# TSC_Schema.net
KiCad netlist of a schematic drawn in EAGLE
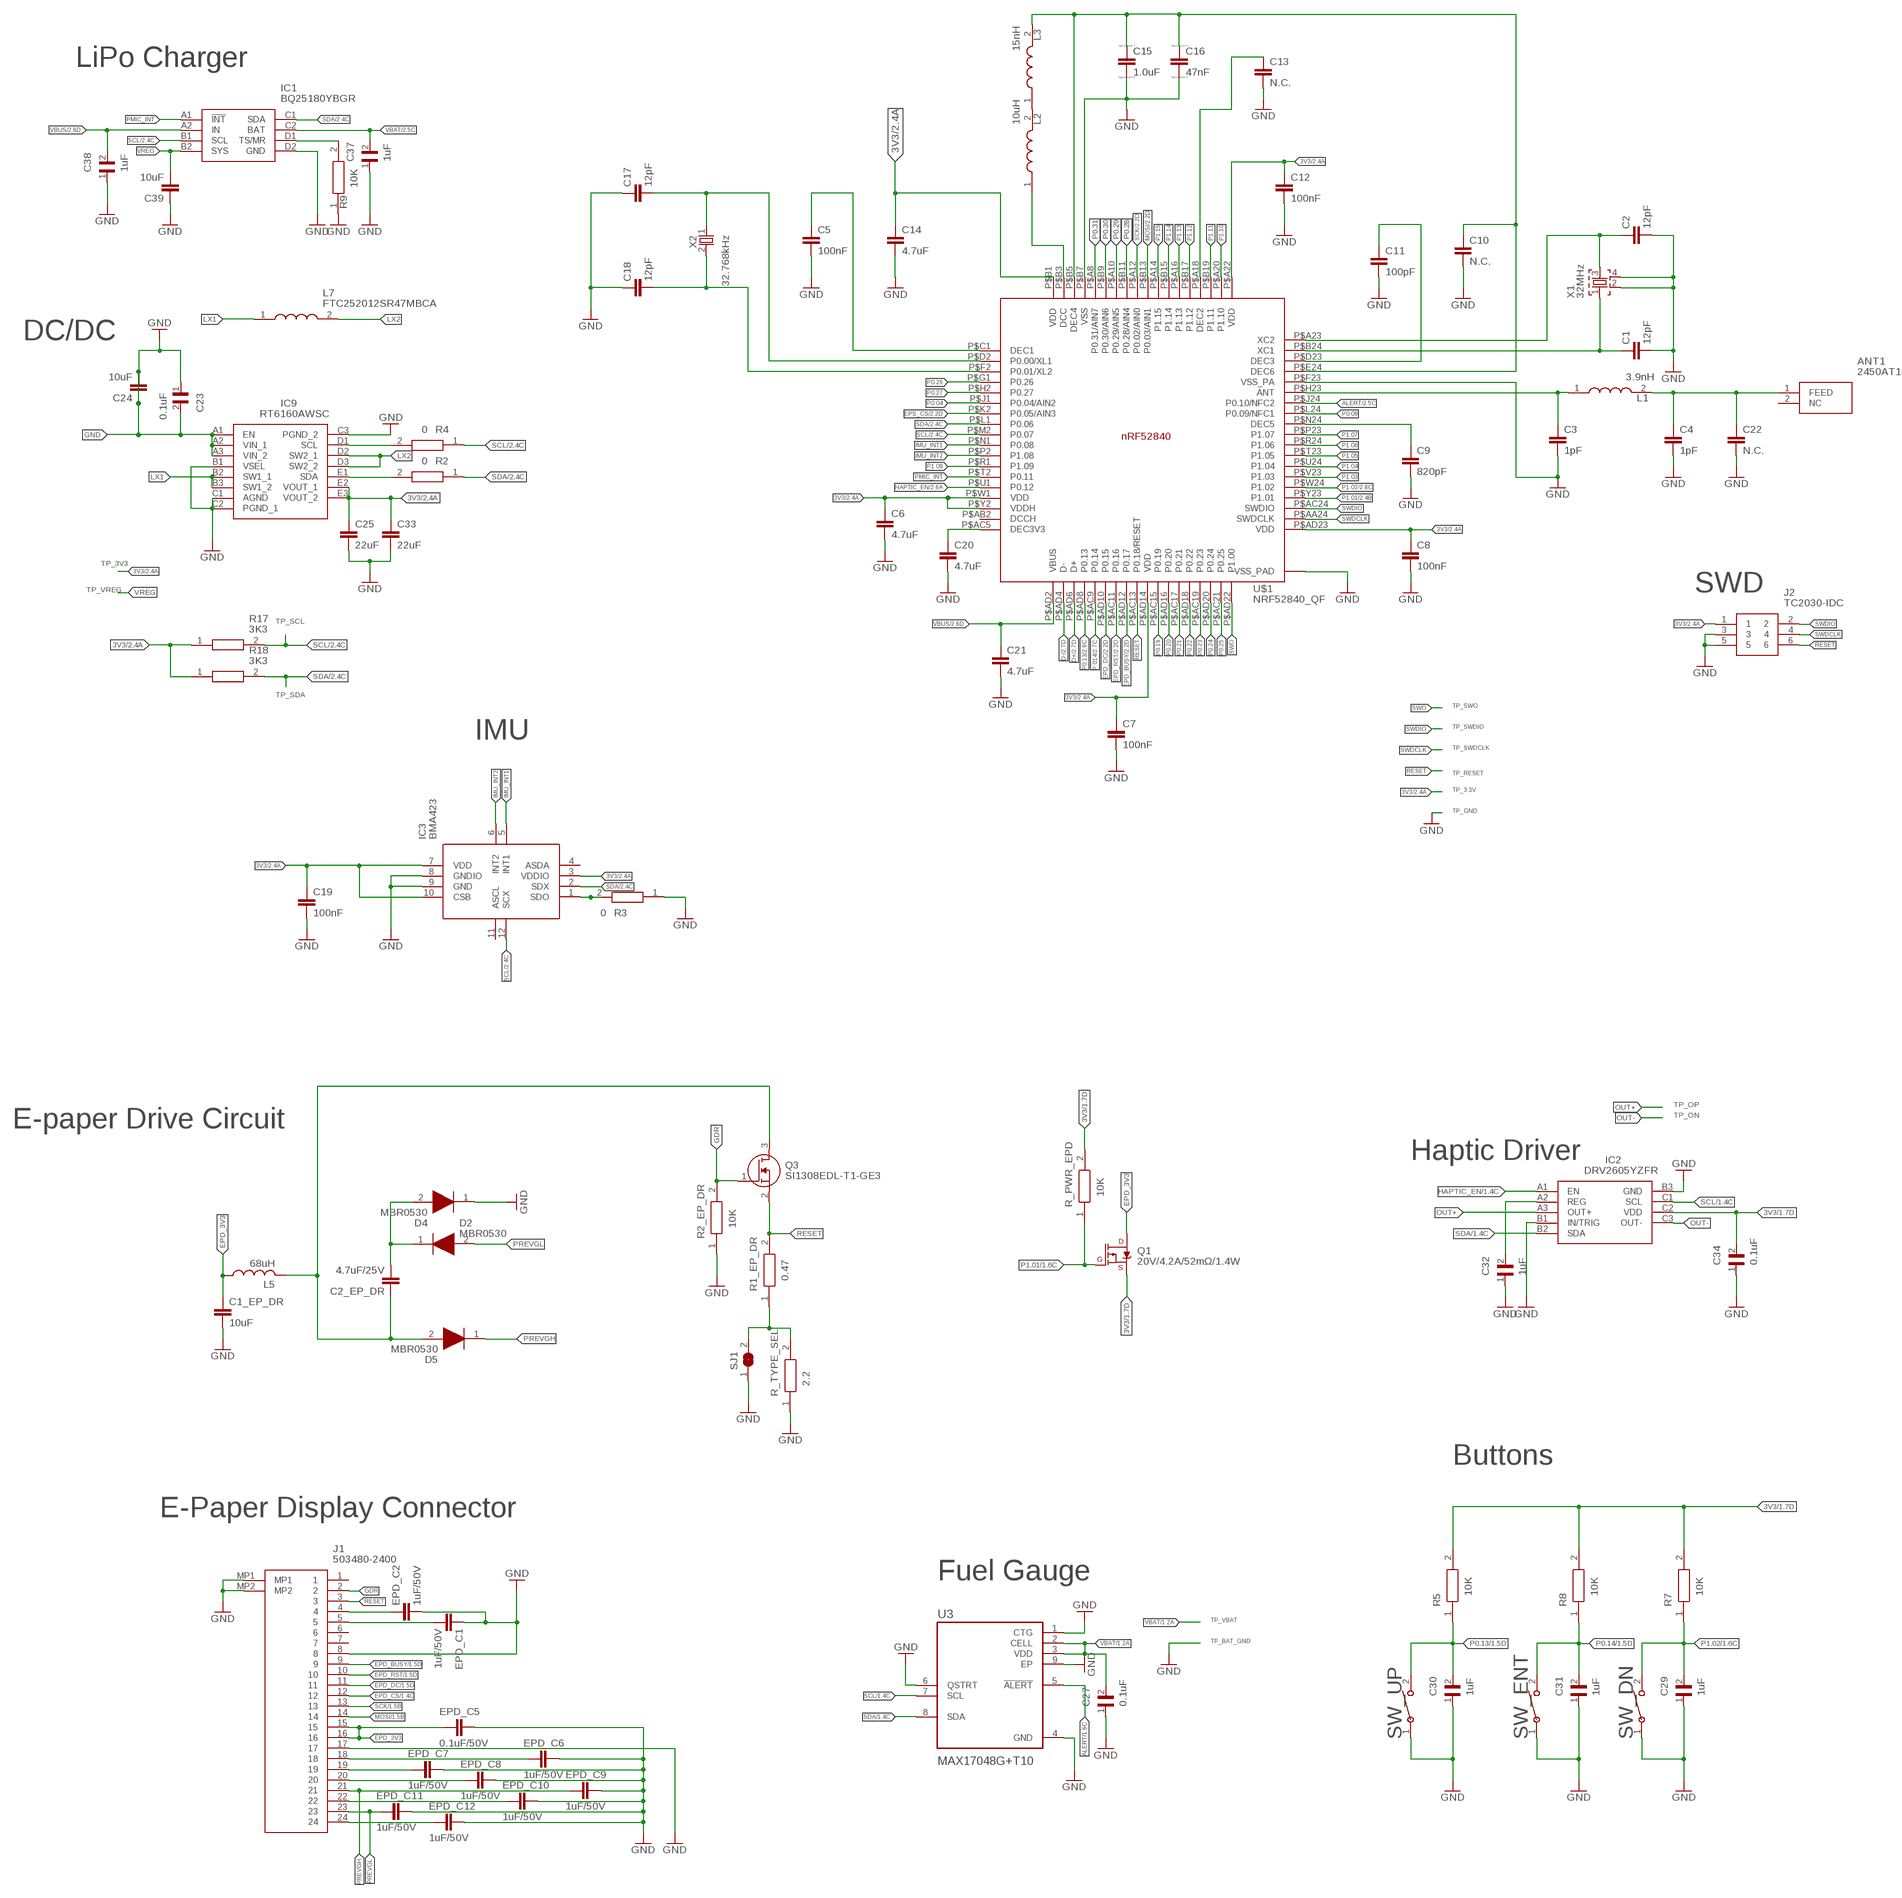
[diagram p0: schematic, sheet 1, part 1 of 2]
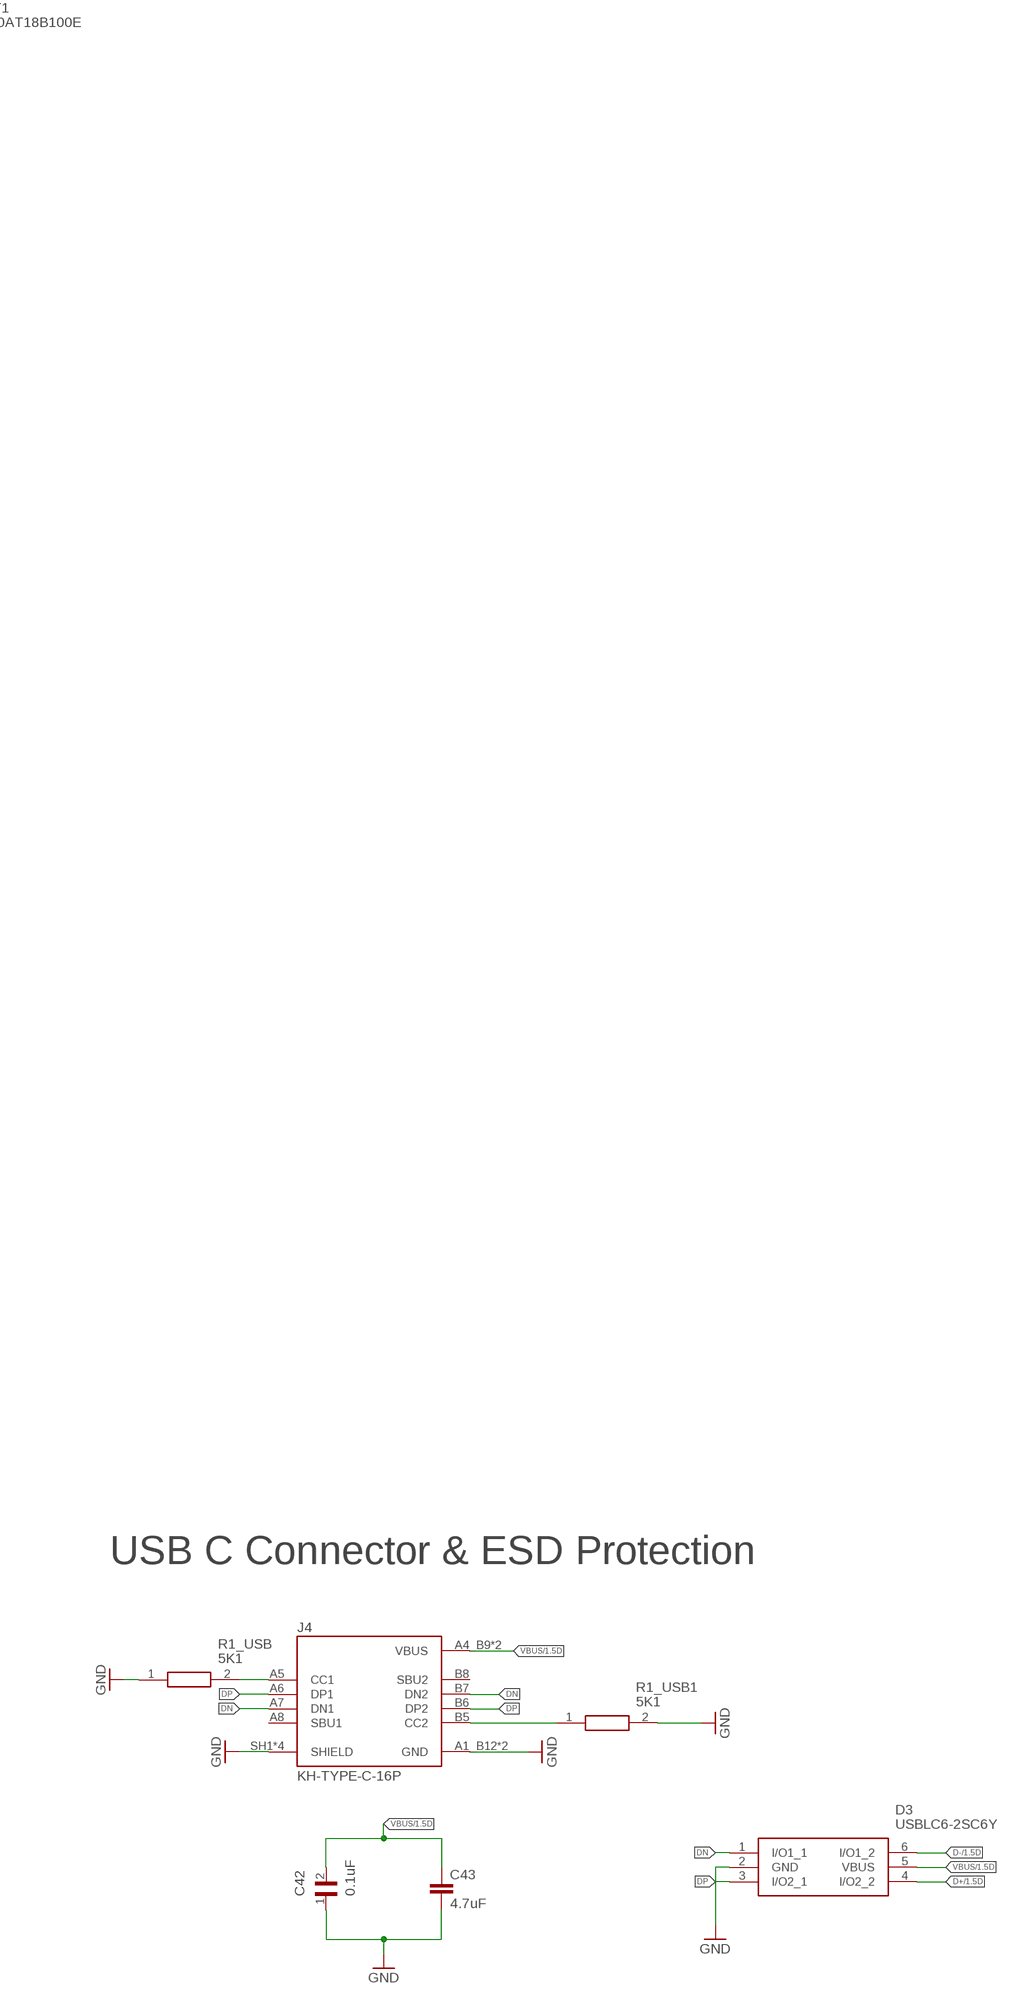
[diagram p1: schematic, sheet 1, part 2 of 2]

(export (version "E")
  (design (tool "Eeschema 10.0.6"))
  (components
    (comp (ref "ANT1")
      (value "2450AT18B100E")
      (footprint "eagle-import:2450AT18B100E_ANTC3216X140N")
      (fields (field (name "MOUSER_PART_NUMBER") "609-2450AT18B100E"))
      (libsource (lib "eagle-import") (part "2450AT18B100E_2450AT18B100E"))
    )
    (comp (ref "C1")
      (value "12pF")
      (footprint "eagle-import:NORDIC_NRF_3_RESC0402_N")
      (libsource (lib "eagle-import") (part "NORDIC_NRF_3_CAPACITOR_0402_N"))
    )
    (comp (ref "C1_EP_DR")
      (value "10uF")
      (footprint "eagle-import:NORDIC_NRF_3_RESC0402_N")
      (libsource (lib "eagle-import") (part "NORDIC_NRF_3_CAPACITOR_0402_N"))
    )
    (comp (ref "C2")
      (value "12pF")
      (footprint "eagle-import:NORDIC_NRF_3_RESC0402_N")
      (libsource (lib "eagle-import") (part "NORDIC_NRF_3_CAPACITOR_0402_N"))
    )
    (comp (ref "C2_EP_DR")
      (value "4.7uF/25V")
      (footprint "eagle-import:NORDIC_NRF_3_RESC0402_N")
      (libsource (lib "eagle-import") (part "NORDIC_NRF_3_CAPACITOR_0402_N"))
    )
    (comp (ref "C3")
      (value "1pF")
      (footprint "eagle-import:NORDIC_NRF_3_RESC0402_N")
      (libsource (lib "eagle-import") (part "NORDIC_NRF_3_CAPACITOR_0402_N"))
    )
    (comp (ref "C4")
      (value "1pF")
      (footprint "eagle-import:NORDIC_NRF_3_RESC0402_N")
      (libsource (lib "eagle-import") (part "NORDIC_NRF_3_CAPACITOR_0402_N"))
    )
    (comp (ref "C5")
      (value "100nF")
      (footprint "eagle-import:NORDIC_NRF_3_RESC0402_N")
      (libsource (lib "eagle-import") (part "NORDIC_NRF_3_CAPACITOR_0402_N"))
    )
    (comp (ref "C6")
      (value "4.7uF")
      (footprint "eagle-import:NORDIC_NRF_3_RESC0402_N")
      (libsource (lib "eagle-import") (part "NORDIC_NRF_3_CAPACITOR_0402_N"))
    )
    (comp (ref "C7")
      (value "100nF")
      (footprint "eagle-import:NORDIC_NRF_3_RESC0402_N")
      (libsource (lib "eagle-import") (part "NORDIC_NRF_3_CAPACITOR_0402_N"))
    )
    (comp (ref "C8")
      (value "100nF")
      (footprint "eagle-import:NORDIC_NRF_3_RESC0402_N")
      (libsource (lib "eagle-import") (part "NORDIC_NRF_3_CAPACITOR_0402_N"))
    )
    (comp (ref "C9")
      (value "820pF")
      (footprint "eagle-import:NORDIC_NRF_3_RESC0402_N")
      (libsource (lib "eagle-import") (part "NORDIC_NRF_3_CAPACITOR_0402_N"))
    )
    (comp (ref "C10")
      (value "N.C.")
      (footprint "eagle-import:NORDIC_NRF_3_RESC0402_N")
      (libsource (lib "eagle-import") (part "NORDIC_NRF_3_CAPACITOR_0402_N"))
    )
    (comp (ref "C11")
      (value "100pF")
      (footprint "eagle-import:NORDIC_NRF_3_RESC0402_N")
      (libsource (lib "eagle-import") (part "NORDIC_NRF_3_CAPACITOR_0402_N"))
    )
    (comp (ref "C12")
      (value "100nF")
      (footprint "eagle-import:NORDIC_NRF_3_RESC0402_N")
      (libsource (lib "eagle-import") (part "NORDIC_NRF_3_CAPACITOR_0402_N"))
    )
    (comp (ref "C13")
      (value "N.C.")
      (footprint "eagle-import:NORDIC_NRF_3_RESC0402_N")
      (libsource (lib "eagle-import") (part "NORDIC_NRF_3_CAPACITOR_0402_N"))
    )
    (comp (ref "C14")
      (value "4.7uF")
      (footprint "eagle-import:NORDIC_NRF_3_RESC0402_N")
      (libsource (lib "eagle-import") (part "NORDIC_NRF_3_CAPACITOR_0402_N"))
    )
    (comp (ref "C15")
      (value "1.0uF")
      (footprint "eagle-import:ESP32_C6_LIBRARY_1_ESP32_WROVER_EAGLE-LTSPICE_C0402")
      (libsource (lib "eagle-import") (part "ESP32_C6_LIBRARY_1_ESP32_WROVER_EAGLE-LTSPICE_CC0402"))
    )
    (comp (ref "C16")
      (value "47nF")
      (footprint "eagle-import:ESP32_C6_LIBRARY_1_ESP32_WROVER_EAGLE-LTSPICE_C0402")
      (libsource (lib "eagle-import") (part "ESP32_C6_LIBRARY_1_ESP32_WROVER_EAGLE-LTSPICE_CC0402"))
    )
    (comp (ref "C17")
      (value "12pF")
      (footprint "eagle-import:NORDIC_NRF_3_RESC0402_N")
      (libsource (lib "eagle-import") (part "NORDIC_NRF_3_CAPACITOR_0402_N"))
    )
    (comp (ref "C18")
      (value "12pF")
      (footprint "eagle-import:NORDIC_NRF_3_RESC0402_N")
      (libsource (lib "eagle-import") (part "NORDIC_NRF_3_CAPACITOR_0402_N"))
    )
    (comp (ref "C19")
      (value "100nF")
      (footprint "eagle-import:NORDIC_NRF_3_RESC0402_N")
      (libsource (lib "eagle-import") (part "NORDIC_NRF_3_CAPACITOR_0402_N"))
    )
    (comp (ref "C20")
      (value "4.7uF")
      (footprint "eagle-import:NORDIC_NRF_3_RESC0402_N")
      (libsource (lib "eagle-import") (part "NORDIC_NRF_3_CAPACITOR_0402_N"))
    )
    (comp (ref "C21")
      (value "4.7uF")
      (footprint "eagle-import:NORDIC_NRF_3_RESC0402_N")
      (libsource (lib "eagle-import") (part "NORDIC_NRF_3_CAPACITOR_0402_N"))
    )
    (comp (ref "C22")
      (value "N.C.")
      (footprint "eagle-import:NORDIC_NRF_3_RESC0402_N")
      (libsource (lib "eagle-import") (part "NORDIC_NRF_3_CAPACITOR_0402_N"))
    )
    (comp (ref "C23")
      (value "0.1uF")
      (footprint "eagle-import:GRM011R60J152KE01L_2_CAPC0201X13N")
      (fields (field (name "MF") "Murata") (field (name "MP") "GRM011R60J152KE01L"))
      (libsource (lib "eagle-import") (part "GRM011R60J152KE01L_2_GRM011R60J152KE01L"))
    )
    (comp (ref "C24")
      (value "10uF")
      (footprint "eagle-import:NORDIC_NRF_3_RESC0402_N")
      (libsource (lib "eagle-import") (part "NORDIC_NRF_3_CAPACITOR_0402_N"))
    )
    (comp (ref "C25")
      (value "22uF")
      (footprint "eagle-import:NORDIC_NRF_3_RESC0402_N")
      (libsource (lib "eagle-import") (part "NORDIC_NRF_3_CAPACITOR_0402_N"))
    )
    (comp (ref "C27")
      (value "0.1uF")
      (footprint "eagle-import:GRM011R60J152KE01L_2_CAPC0201X13N")
      (fields (field (name "MF") "Murata") (field (name "MP") "GRM011R60J152KE01L"))
      (libsource (lib "eagle-import") (part "GRM011R60J152KE01L_2_GRM011R60J152KE01L"))
    )
    (comp (ref "C29")
      (value "1uF")
      (footprint "eagle-import:GRM011R60J152KE01L_2_CAPC0201X13N")
      (fields (field (name "MF") "Murata") (field (name "MP") "GRM011R60J152KE01L"))
      (libsource (lib "eagle-import") (part "GRM011R60J152KE01L_2_GRM011R60J152KE01L"))
    )
    (comp (ref "C30")
      (value "1uF")
      (footprint "eagle-import:GRM011R60J152KE01L_2_CAPC0201X13N")
      (fields (field (name "MF") "Murata") (field (name "MP") "GRM011R60J152KE01L"))
      (libsource (lib "eagle-import") (part "GRM011R60J152KE01L_2_GRM011R60J152KE01L"))
    )
    (comp (ref "C31")
      (value "1uF")
      (footprint "eagle-import:GRM011R60J152KE01L_2_CAPC0201X13N")
      (fields (field (name "MF") "Murata") (field (name "MP") "GRM011R60J152KE01L"))
      (libsource (lib "eagle-import") (part "GRM011R60J152KE01L_2_GRM011R60J152KE01L"))
    )
    (comp (ref "C32")
      (value "1uF")
      (footprint "eagle-import:GRM011R60J152KE01L_2_CAPC0201X13N")
      (fields (field (name "MF") "Murata") (field (name "MP") "GRM011R60J152KE01L"))
      (libsource (lib "eagle-import") (part "GRM011R60J152KE01L_2_GRM011R60J152KE01L"))
    )
    (comp (ref "C33")
      (value "22uF")
      (footprint "eagle-import:NORDIC_NRF_3_RESC0402_N")
      (libsource (lib "eagle-import") (part "NORDIC_NRF_3_CAPACITOR_0402_N"))
    )
    (comp (ref "C34")
      (value "0.1uF")
      (footprint "eagle-import:GRM011R60J152KE01L_2_CAPC0201X13N")
      (fields (field (name "MF") "Murata") (field (name "MP") "GRM011R60J152KE01L"))
      (libsource (lib "eagle-import") (part "GRM011R60J152KE01L_2_GRM011R60J152KE01L"))
    )
    (comp (ref "C37")
      (value "1uF")
      (footprint "eagle-import:GRM011R60J152KE01L_2_CAPC0201X13N")
      (fields (field (name "MF") "Murata") (field (name "MP") "GRM011R60J152KE01L"))
      (libsource (lib "eagle-import") (part "GRM011R60J152KE01L_2_GRM011R60J152KE01L"))
    )
    (comp (ref "C38")
      (value "1uF")
      (footprint "eagle-import:GRM011R60J152KE01L_2_CAPC0201X13N")
      (fields (field (name "MF") "Murata") (field (name "MP") "GRM011R60J152KE01L"))
      (libsource (lib "eagle-import") (part "GRM011R60J152KE01L_2_GRM011R60J152KE01L"))
    )
    (comp (ref "C39")
      (value "10uF")
      (footprint "eagle-import:NORDIC_NRF_3_RESC0402_N")
      (libsource (lib "eagle-import") (part "NORDIC_NRF_3_CAPACITOR_0402_N"))
    )
    (comp (ref "C42")
      (value "0.1uF")
      (footprint "eagle-import:GRM011R60J152KE01L_2_CAPC0201X13N")
      (fields (field (name "MF") "Murata") (field (name "MP") "GRM011R60J152KE01L"))
      (libsource (lib "eagle-import") (part "GRM011R60J152KE01L_2_GRM011R60J152KE01L"))
    )
    (comp (ref "C43")
      (value "4.7uF")
      (footprint "eagle-import:NORDIC_NRF_3_RESC0402_N")
      (libsource (lib "eagle-import") (part "NORDIC_NRF_3_CAPACITOR_0402_N"))
    )
    (comp (ref "D2")
      (value "MBR0530")
      (footprint "eagle-import:ESP32_C6_LIBRARY_5_SOD3716X135N")
      (fields (field (name "MF") "ON Semiconductor"))
      (libsource (lib "eagle-import") (part "ESP32_C6_LIBRARY_5_MBR0530"))
    )
    (comp (ref "D3")
      (value "USBLC6-2SC6Y")
      (footprint "eagle-import:ESP32_C6_LIBRARY_3_SOT95P280X145-6N")
      (fields (field (name "MF") "STMicroelectronics"))
      (libsource (lib "eagle-import") (part "ESP32_C6_LIBRARY_3_USBLC6-2SC6Y"))
    )
    (comp (ref "D4")
      (value "MBR0530")
      (footprint "eagle-import:ESP32_C6_LIBRARY_5_SOD3716X135N")
      (fields (field (name "MF") "ON Semiconductor"))
      (libsource (lib "eagle-import") (part "ESP32_C6_LIBRARY_5_MBR0530"))
    )
    (comp (ref "D5")
      (value "MBR0530")
      (footprint "eagle-import:ESP32_C6_LIBRARY_5_SOD3716X135N")
      (fields (field (name "MF") "ON Semiconductor"))
      (libsource (lib "eagle-import") (part "ESP32_C6_LIBRARY_5_MBR0530"))
    )
    (comp (ref "EPD_C1")
      (value "1uF/50V")
      (footprint "eagle-import:NORDIC_NRF_3_RESC0402_N")
      (libsource (lib "eagle-import") (part "NORDIC_NRF_3_CAPACITOR_0402_N"))
    )
    (comp (ref "EPD_C2")
      (value "1uF/50V")
      (footprint "eagle-import:NORDIC_NRF_3_RESC0402_N")
      (libsource (lib "eagle-import") (part "NORDIC_NRF_3_CAPACITOR_0402_N"))
    )
    (comp (ref "EPD_C5")
      (value "0.1uF/50V")
      (footprint "eagle-import:NORDIC_NRF_3_RESC0402_N")
      (libsource (lib "eagle-import") (part "NORDIC_NRF_3_CAPACITOR_0402_N"))
    )
    (comp (ref "EPD_C6")
      (value "1uF/50V")
      (footprint "eagle-import:NORDIC_NRF_3_RESC0402_N")
      (libsource (lib "eagle-import") (part "NORDIC_NRF_3_CAPACITOR_0402_N"))
    )
    (comp (ref "EPD_C7")
      (value "1uF/50V")
      (footprint "eagle-import:NORDIC_NRF_3_RESC0402_N")
      (libsource (lib "eagle-import") (part "NORDIC_NRF_3_CAPACITOR_0402_N"))
    )
    (comp (ref "EPD_C8")
      (value "1uF/50V")
      (footprint "eagle-import:NORDIC_NRF_3_RESC0402_N")
      (libsource (lib "eagle-import") (part "NORDIC_NRF_3_CAPACITOR_0402_N"))
    )
    (comp (ref "EPD_C9")
      (value "1uF/50V")
      (footprint "eagle-import:NORDIC_NRF_3_RESC0402_N")
      (libsource (lib "eagle-import") (part "NORDIC_NRF_3_CAPACITOR_0402_N"))
    )
    (comp (ref "EPD_C10")
      (value "1uF/50V")
      (footprint "eagle-import:NORDIC_NRF_3_RESC0402_N")
      (libsource (lib "eagle-import") (part "NORDIC_NRF_3_CAPACITOR_0402_N"))
    )
    (comp (ref "EPD_C11")
      (value "1uF/50V")
      (footprint "eagle-import:NORDIC_NRF_3_RESC0402_N")
      (libsource (lib "eagle-import") (part "NORDIC_NRF_3_CAPACITOR_0402_N"))
    )
    (comp (ref "EPD_C12")
      (value "1uF/50V")
      (footprint "eagle-import:NORDIC_NRF_3_RESC0402_N")
      (libsource (lib "eagle-import") (part "NORDIC_NRF_3_CAPACITOR_0402_N"))
    )
    (comp (ref "IC1")
      (value "BQ25180YBGR")
      (footprint "eagle-import:BQ25180YBGR_BGA8C40P2X4_100X155X50")
      (fields (field (name "MOUSER_PART_NUMBER") "595-BQ25180YBGR"))
      (libsource (lib "eagle-import") (part "BQ25180YBGR_BQ25180YBGR"))
    )
    (comp (ref "IC2")
      (value "DRV2605YZFR")
      (footprint "eagle-import:DRV2605YZFR_BGA9C50P3X3_144X144X62")
      (libsource (lib "eagle-import") (part "DRV2605YZFR_DRV2605YZFR"))
    )
    (comp (ref "IC3")
      (value "BMA423")
      (footprint "eagle-import:BMA423_BMA423")
      (fields (field (name "MOUSER_PART_NUMBER") "262-BMA423"))
      (libsource (lib "eagle-import") (part "BMA423_BMA423"))
    )
    (comp (ref "IC9")
      (value "RT6160AWSC")
      (footprint "eagle-import:RT6160AWSC_BGA15C40P3X5_140X230X60")
      (fields (field (name "MOUSER_PART_NUMBER") "835-RT6160AWSC"))
      (libsource (lib "eagle-import") (part "RT6160AWSC_RT6160AWSC"))
    )
    (comp (ref "J1")
      (value "503480-2400")
      (footprint "eagle-import:503480-2400_5034802400")
      (fields (field (name "MOUSER_PART_NUMBER") "538-503480-2400"))
      (libsource (lib "eagle-import") (part "503480-2400_503480-2400"))
    )
    (comp (ref "J2")
      (value "TC2030-IDC")
      (footprint "eagle-import:TC2030-IDC_TC2030IDC")
      (libsource (lib "eagle-import") (part "TC2030-IDC_TC2030-IDC"))
    )
    (comp (ref "J4")
      (value "KH-TYPE-C-16P")
      (footprint "eagle-import:KH-TYPE-C-16P_KINGHELM_KH-TYPE-C-16P")
      (fields (field (name "MF") "kinghelm"))
      (libsource (lib "eagle-import") (part "KH-TYPE-C-16P_KH-TYPE-C-16P"))
    )
    (comp (ref "L1")
      (value "3.9nH")
      (footprint "eagle-import:MLP2016SR47MT0S1_INDC2016X100N")
      (fields (field (name "MANUFACTURER_PART_NUMBER") "FTC252012SR47MBCA"))
      (libsource (lib "eagle-import") (part "MLP2016SR47MT0S1_FTC252012SR47MBCA"))
    )
    (comp (ref "L2")
      (value "10uH")
      (footprint "eagle-import:MLP2016SR47MT0S1_INDC2016X100N")
      (fields (field (name "MANUFACTURER_PART_NUMBER") "FTC252012SR47MBCA"))
      (libsource (lib "eagle-import") (part "MLP2016SR47MT0S1_FTC252012SR47MBCA"))
    )
    (comp (ref "L3")
      (value "15nH")
      (footprint "eagle-import:MLP2016SR47MT0S1_INDC2016X100N")
      (fields (field (name "MANUFACTURER_PART_NUMBER") "FTC252012SR47MBCA"))
      (libsource (lib "eagle-import") (part "MLP2016SR47MT0S1_FTC252012SR47MBCA"))
    )
    (comp (ref "L5")
      (value "68uH")
      (footprint "eagle-import:NORDIC_NRF_2_RESC0402_L")
      (libsource (lib "eagle-import") (part "NORDIC_NRF_2_INDUCTOR_0402_L"))
    )
    (comp (ref "L7")
      (value "FTC252012SR47MBCA")
      (footprint "eagle-import:MLP2016SR47MT0S1_INDC2016X100N")
      (libsource (lib "eagle-import") (part "MLP2016SR47MT0S1_FTC252012SR47MBCA"))
    )
    (comp (ref "Q1")
      (value "20V/4.2A/52mΩ/1.4W")
      (footprint "eagle-import:ESP32_C6_LIBRARY_4_ESP32_C6_LIBRARY_4_ESP32_C6_LIBRARY_4_ESP32_C6_LIBRARY_4_ESP32_WROVER_SPARKFUN-DISCRETESEMI_SOT23-3")
      (libsource (lib "eagle-import") (part "ESP32_C6_LIBRARY_4_ESP32_WROVER_SPARKFUN-DISCRETESEMI_MOSFET_PCH-DMG2305UX-7"))
    )
    (comp (ref "Q3")
      (value "SI1308EDL-T1-GE3")
      (footprint "eagle-import:ESP32_C6_LIBRARY_6_SOT65P210X110-3N")
      (fields (field (name "MF") "Vishay Siliconix"))
      (libsource (lib "eagle-import") (part "ESP32_C6_LIBRARY_6_SI1308EDL-T1-GE3"))
    )
    (comp (ref "R1_EP_DR")
      (value "0.47")
      (footprint "eagle-import:CPF0201D7K68C1_0201")
      (libsource (lib "eagle-import") (part "CPF0201D7K68C1_CPF0201D7K68C1"))
    )
    (comp (ref "R1_USB")
      (value "5K1")
      (footprint "eagle-import:CPF0201D7K68C1_0201")
      (libsource (lib "eagle-import") (part "CPF0201D7K68C1_CPF0201D7K68C1"))
    )
    (comp (ref "R1_USB1")
      (value "5K1")
      (footprint "eagle-import:CPF0201D7K68C1_0201")
      (libsource (lib "eagle-import") (part "CPF0201D7K68C1_CPF0201D7K68C1"))
    )
    (comp (ref "R2")
      (value "0")
      (footprint "eagle-import:CPF0201D7K68C1_0201")
      (libsource (lib "eagle-import") (part "CPF0201D7K68C1_CPF0201D7K68C1"))
    )
    (comp (ref "R2_EP_DR")
      (value "10K")
      (footprint "eagle-import:CPF0201D7K68C1_0201")
      (libsource (lib "eagle-import") (part "CPF0201D7K68C1_CPF0201D7K68C1"))
    )
    (comp (ref "R3")
      (value "0")
      (footprint "eagle-import:CPF0201D7K68C1_0201")
      (libsource (lib "eagle-import") (part "CPF0201D7K68C1_CPF0201D7K68C1"))
    )
    (comp (ref "R4")
      (value "0")
      (footprint "eagle-import:CPF0201D7K68C1_0201")
      (libsource (lib "eagle-import") (part "CPF0201D7K68C1_CPF0201D7K68C1"))
    )
    (comp (ref "R5")
      (value "10K")
      (footprint "eagle-import:CPF0201D7K68C1_0201")
      (libsource (lib "eagle-import") (part "CPF0201D7K68C1_CPF0201D7K68C1"))
    )
    (comp (ref "R7")
      (value "10K")
      (footprint "eagle-import:CPF0201D7K68C1_0201")
      (libsource (lib "eagle-import") (part "CPF0201D7K68C1_CPF0201D7K68C1"))
    )
    (comp (ref "R8")
      (value "10K")
      (footprint "eagle-import:CPF0201D7K68C1_0201")
      (libsource (lib "eagle-import") (part "CPF0201D7K68C1_CPF0201D7K68C1"))
    )
    (comp (ref "R9")
      (value "10K")
      (footprint "eagle-import:CPF0201D7K68C1_0201")
      (libsource (lib "eagle-import") (part "CPF0201D7K68C1_CPF0201D7K68C1"))
    )
    (comp (ref "R17")
      (value "3K3")
      (footprint "eagle-import:CPF0201D7K68C1_0201")
      (libsource (lib "eagle-import") (part "CPF0201D7K68C1_CPF0201D7K68C1"))
    )
    (comp (ref "R18")
      (value "3K3")
      (footprint "eagle-import:CPF0201D7K68C1_0201")
      (libsource (lib "eagle-import") (part "CPF0201D7K68C1_CPF0201D7K68C1"))
    )
    (comp (ref "R_PWR_EPD")
      (value "10K")
      (footprint "eagle-import:CPF0201D7K68C1_0201")
      (libsource (lib "eagle-import") (part "CPF0201D7K68C1_CPF0201D7K68C1"))
    )
    (comp (ref "R_TYPE_SEL")
      (value "2.2")
      (footprint "eagle-import:CPF0201D7K68C1_0201")
      (libsource (lib "eagle-import") (part "CPF0201D7K68C1_CPF0201D7K68C1"))
    )
    (comp (ref "SJ1")
      (value "ESP32_C6_LIBRARY_7_JUMPER_SJ")
      (footprint "eagle-import:ESP32_C6_LIBRARY_7_JUMPER_SJ")
      (libsource (lib "eagle-import") (part "ESP32_C6_LIBRARY_7_JUMPER_SJ"))
    )
    (comp (ref "SW_DN")
      (value "2025-10-22_07-23-44_LIBRARY_EVP-AKE31ASW_EVP-AKE31A_PAN")
      (footprint "eagle-import:2025-10-22_07-23-44_LIBRARY_SW_EVP-AKE31A_PAN")
      (fields
        (field (name "MANUFACTURER_PART_NUMBER") "EVP-AKE31A")
        (field (name "COPYRIGHT") "Copyright (C) 2025 Ultra Librarian. All rights reserved.")
      )
      (libsource (lib "eagle-import") (part "2025-10-22_07-23-44_LIBRARY_EVP-AKE31ASW_EVP-AKE31A_PAN"))
    )
    (comp (ref "SW_ENT")
      (value "2025-10-22_07-23-44_LIBRARY_EVP-AKE31ASW_EVP-AKE31A_PAN")
      (footprint "eagle-import:2025-10-22_07-23-44_LIBRARY_SW_EVP-AKE31A_PAN")
      (fields
        (field (name "MANUFACTURER_PART_NUMBER") "EVP-AKE31A")
        (field (name "COPYRIGHT") "Copyright (C) 2025 Ultra Librarian. All rights reserved.")
      )
      (libsource (lib "eagle-import") (part "2025-10-22_07-23-44_LIBRARY_EVP-AKE31ASW_EVP-AKE31A_PAN"))
    )
    (comp (ref "SW_UP")
      (value "2025-10-22_07-23-44_LIBRARY_EVP-AKE31ASW_EVP-AKE31A_PAN")
      (footprint "eagle-import:2025-10-22_07-23-44_LIBRARY_SW_EVP-AKE31A_PAN")
      (fields
        (field (name "MANUFACTURER_PART_NUMBER") "EVP-AKE31A")
        (field (name "COPYRIGHT") "Copyright (C) 2025 Ultra Librarian. All rights reserved.")
      )
      (libsource (lib "eagle-import") (part "2025-10-22_07-23-44_LIBRARY_EVP-AKE31ASW_EVP-AKE31A_PAN"))
    )
    (comp (ref "U$1")
      (value "NRF52840_QF")
      (footprint "eagle-import:NORDIC_NRF_4_AQFN50P700X700X85_HS-74N")
      (libsource (lib "eagle-import") (part "NORDIC_NRF_4_NRF52840_QF"))
    )
    (comp (ref "U3")
      (value "MAX17048G+T10")
      (footprint "eagle-import:ESP32_C6_LIBRARY_SON50P200X200X80-9N")
      (fields (field (name "MF") "Analog Devices"))
      (libsource (lib "eagle-import") (part "ESP32_C6_LIBRARY_MAX17048G+T10"))
    )
    (comp (ref "X1")
      (value "32MHz")
      (footprint "eagle-import:NORDIC_NRF_BT-XTAL_2016_N")
      (libsource (lib "eagle-import") (part "NORDIC_NRF_XTAL_32MHZ"))
    )
    (comp (ref "X2")
      (value "32.768kHz")
      (footprint "eagle-import:NORDIC_NRF_1_XTAL_3215_N")
      (libsource (lib "eagle-import") (part "NORDIC_NRF_1_XTAL_32KHZ"))
    )
  )
  (nets
    (net (code "1") (name "3V3{slash}1.7D") (class "Default")
      (node (ref "C34") (pin "2") (pinfunction "2_2") (pintype "passive"))
      (node (ref "IC2") (pin "C2") (pinfunction "VDD_C2") (pintype "bidirectional"))
      (node (ref "Q1") (pin "2") (pinfunction "S_2") (pintype "bidirectional"))
      (node (ref "R5") (pin "2") (pinfunction "2_2") (pintype "bidirectional"))
      (node (ref "R7") (pin "2") (pinfunction "2_2") (pintype "bidirectional"))
      (node (ref "R8") (pin "2") (pinfunction "2_2") (pintype "bidirectional"))
      (node (ref "R_PWR_EPD") (pin "2") (pinfunction "2_2") (pintype "bidirectional"))
    )
    (net (code "2") (name "3V3{slash}2.4A") (class "Default")
      (node (ref "C12") (pin "1") (pinfunction "1_1") (pintype "passive"))
      (node (ref "C14") (pin "1") (pinfunction "1_1") (pintype "passive"))
      (node (ref "C19") (pin "1") (pinfunction "1_1") (pintype "passive"))
      (node (ref "C25") (pin "1") (pinfunction "1_1") (pintype "passive"))
      (node (ref "C33") (pin "1") (pinfunction "1_1") (pintype "passive"))
      (node (ref "C6") (pin "1") (pinfunction "1_1") (pintype "passive"))
      (node (ref "C7") (pin "1") (pinfunction "1_1") (pintype "passive"))
      (node (ref "C8") (pin "1") (pinfunction "1_1") (pintype "passive"))
      (node (ref "IC3") (pin "10") (pinfunction "CSB_10") (pintype "bidirectional"))
      (node (ref "IC3") (pin "3") (pinfunction "VDDIO_3") (pintype "bidirectional"))
      (node (ref "IC3") (pin "7") (pinfunction "VDD_7") (pintype "bidirectional"))
      (node (ref "IC9") (pin "E2") (pinfunction "VOUT_1_E2") (pintype "bidirectional"))
      (node (ref "IC9") (pin "E3") (pinfunction "VOUT_2_E3") (pintype "bidirectional"))
      (node (ref "J2") (pin "1") (pinfunction "1_1") (pintype "bidirectional"))
      (node (ref "R17") (pin "1") (pinfunction "1_1") (pintype "bidirectional"))
      (node (ref "R18") (pin "1") (pinfunction "1_1") (pintype "bidirectional"))
      (node (ref "U$1") (pin "P$A22") (pinfunction "VDD_P$A22") (pintype "power_in"))
      (node (ref "U$1") (pin "P$AD14") (pinfunction "VDD_P$AD14") (pintype "power_in"))
      (node (ref "U$1") (pin "P$AD23") (pinfunction "VDD_P$AD23") (pintype "power_in"))
      (node (ref "U$1") (pin "P$B1") (pinfunction "VDD_P$B1") (pintype "power_in"))
      (node (ref "U$1") (pin "P$W1") (pinfunction "VDD_P$W1") (pintype "power_in"))
      (node (ref "U$1") (pin "P$Y2") (pinfunction "VDDH_P$Y2") (pintype "power_in"))
    )
    (net (code "3") (name "ALERT{slash}1.6C") (class "Default")
      (node (ref "U3") (pin "5") (pinfunction "~{ALERT}_5") (pintype "output"))
    )
    (net (code "4") (name "ALERT{slash}2.5C") (class "Default")
      (node (ref "U$1") (pin "P$J24") (pinfunction "P0.10/NFC2_P$J24") (pintype "bidirectional"))
    )
    (net (code "5") (name "D+{slash}1.5D") (class "Default")
      (node (ref "D3") (pin "4") (pinfunction "I/O2_2_4") (pintype "bidirectional"))
    )
    (net (code "6") (name "D+{slash}2.7D") (class "Default")
      (node (ref "U$1") (pin "P$AD6") (pinfunction "D+_P$AD6") (pintype "bidirectional"))
    )
    (net (code "7") (name "D-{slash}1.5D") (class "Default")
      (node (ref "D3") (pin "6") (pinfunction "I/O1_2_6") (pintype "bidirectional"))
    )
    (net (code "8") (name "D-{slash}2.7D") (class "Default")
      (node (ref "U$1") (pin "P$AD4") (pinfunction "D-_P$AD4") (pintype "bidirectional"))
    )
    (net (code "9") (name "DN") (class "Default")
      (node (ref "D3") (pin "1") (pinfunction "I/O1_1_1") (pintype "bidirectional"))
      (node (ref "J4") (pin "A7") (pinfunction "DN1_A7") (pintype "bidirectional"))
      (node (ref "J4") (pin "B7") (pinfunction "DN2_B7") (pintype "bidirectional"))
    )
    (net (code "10") (name "DP") (class "Default")
      (node (ref "D3") (pin "3") (pinfunction "I/O2_1_3") (pintype "bidirectional"))
      (node (ref "J4") (pin "A6") (pinfunction "DP1_A6") (pintype "bidirectional"))
      (node (ref "J4") (pin "B6") (pinfunction "DP2_B6") (pintype "bidirectional"))
    )
    (net (code "11") (name "EPD_3V3") (class "Default")
      (node (ref "C1_EP_DR") (pin "1") (pinfunction "1_1") (pintype "passive"))
      (node (ref "EPD_C5") (pin "2") (pinfunction "2_2") (pintype "passive"))
      (node (ref "J1") (pin "15") (pinfunction "15_15") (pintype "bidirectional"))
      (node (ref "J1") (pin "16") (pinfunction "16_16") (pintype "bidirectional"))
      (node (ref "L5") (pin "1") (pinfunction "1_1") (pintype "passive"))
      (node (ref "Q1") (pin "3") (pinfunction "D_3") (pintype "bidirectional"))
    )
    (net (code "12") (name "EPD_BUSY{slash}1.5D") (class "Default")
      (node (ref "J1") (pin "9") (pinfunction "9_9") (pintype "bidirectional"))
    )
    (net (code "13") (name "EPD_BUSY{slash}2.2D") (class "Default")
      (node (ref "U$1") (pin "P$AD12") (pinfunction "P0.17_P$AD12") (pintype "bidirectional"))
    )
    (net (code "14") (name "EPD_CS{slash}1.4C") (class "Default")
      (node (ref "J1") (pin "12") (pinfunction "12_12") (pintype "bidirectional"))
    )
    (net (code "15") (name "EPD_DC{slash}1.5D") (class "Default")
      (node (ref "J1") (pin "11") (pinfunction "11_11") (pintype "bidirectional"))
    )
    (net (code "16") (name "EPD_DC{slash}2.2D") (class "Default")
      (node (ref "U$1") (pin "P$AD10") (pinfunction "P0.15_P$AD10") (pintype "bidirectional"))
    )
    (net (code "17") (name "EPD_RST{slash}1.5D") (class "Default")
      (node (ref "J1") (pin "10") (pinfunction "10_10") (pintype "bidirectional"))
    )
    (net (code "18") (name "EPD_RST{slash}2.2D") (class "Default")
      (node (ref "U$1") (pin "P$AC11") (pinfunction "P0.16_P$AC11") (pintype "bidirectional"))
    )
    (net (code "19") (name "EPS_CS{slash}2.2D") (class "Default")
      (node (ref "U$1") (pin "P$K2") (pinfunction "P0.05/AIN3_P$K2") (pintype "bidirectional"))
    )
    (net (code "20") (name "GDR") (class "Default")
      (node (ref "J1") (pin "2") (pinfunction "2_2") (pintype "bidirectional"))
      (node (ref "Q3") (pin "1") (pinfunction "G_1") (pintype "bidirectional"))
      (node (ref "R2_EP_DR") (pin "2") (pinfunction "2_2") (pintype "bidirectional"))
    )
    (net (code "21") (name "GND") (class "Default")
      (node (ref "C1") (pin "2") (pinfunction "2_2") (pintype "passive"))
      (node (ref "C10") (pin "2") (pinfunction "2_2") (pintype "passive"))
      (node (ref "C11") (pin "2") (pinfunction "2_2") (pintype "passive"))
      (node (ref "C12") (pin "2") (pinfunction "2_2") (pintype "passive"))
      (node (ref "C13") (pin "2") (pinfunction "2_2") (pintype "passive"))
      (node (ref "C14") (pin "2") (pinfunction "2_2") (pintype "passive"))
      (node (ref "C15") (pin "2") (pinfunction "2_2") (pintype "passive"))
      (node (ref "C16") (pin "2") (pinfunction "2_2") (pintype "passive"))
      (node (ref "C17") (pin "1") (pinfunction "1_1") (pintype "passive"))
      (node (ref "C18") (pin "1") (pinfunction "1_1") (pintype "passive"))
      (node (ref "C19") (pin "2") (pinfunction "2_2") (pintype "passive"))
      (node (ref "C1_EP_DR") (pin "2") (pinfunction "2_2") (pintype "passive"))
      (node (ref "C2") (pin "2") (pinfunction "2_2") (pintype "passive"))
      (node (ref "C20") (pin "2") (pinfunction "2_2") (pintype "passive"))
      (node (ref "C21") (pin "2") (pinfunction "2_2") (pintype "passive"))
      (node (ref "C22") (pin "2") (pinfunction "2_2") (pintype "passive"))
      (node (ref "C23") (pin "1") (pinfunction "1_1") (pintype "passive"))
      (node (ref "C23") (pin "2") (pinfunction "2_2") (pintype "passive"))
      (node (ref "C24") (pin "1") (pinfunction "1_1") (pintype "passive"))
      (node (ref "C24") (pin "2") (pinfunction "2_2") (pintype "passive"))
      (node (ref "C25") (pin "2") (pinfunction "2_2") (pintype "passive"))
      (node (ref "C27") (pin "1") (pinfunction "1_1") (pintype "passive"))
      (node (ref "C29") (pin "1") (pinfunction "1_1") (pintype "passive"))
      (node (ref "C3") (pin "2") (pinfunction "2_2") (pintype "passive"))
      (node (ref "C30") (pin "1") (pinfunction "1_1") (pintype "passive"))
      (node (ref "C31") (pin "1") (pinfunction "1_1") (pintype "passive"))
      (node (ref "C32") (pin "1") (pinfunction "1_1") (pintype "passive"))
      (node (ref "C33") (pin "2") (pinfunction "2_2") (pintype "passive"))
      (node (ref "C34") (pin "1") (pinfunction "1_1") (pintype "passive"))
      (node (ref "C37") (pin "1") (pinfunction "1_1") (pintype "passive"))
      (node (ref "C38") (pin "1") (pinfunction "1_1") (pintype "passive"))
      (node (ref "C39") (pin "1") (pinfunction "1_1") (pintype "passive"))
      (node (ref "C4") (pin "2") (pinfunction "2_2") (pintype "passive"))
      (node (ref "C42") (pin "1") (pinfunction "1_1") (pintype "passive"))
      (node (ref "C43") (pin "2") (pinfunction "2_2") (pintype "passive"))
      (node (ref "C5") (pin "2") (pinfunction "2_2") (pintype "passive"))
      (node (ref "C6") (pin "2") (pinfunction "2_2") (pintype "passive"))
      (node (ref "C7") (pin "2") (pinfunction "2_2") (pintype "passive"))
      (node (ref "C8") (pin "2") (pinfunction "2_2") (pintype "passive"))
      (node (ref "C9") (pin "2") (pinfunction "2_2") (pintype "passive"))
      (node (ref "D3") (pin "2") (pinfunction "GND_2") (pintype "bidirectional"))
      (node (ref "D4") (pin "1") (pinfunction "K_1") (pintype "bidirectional"))
      (node (ref "EPD_C1") (pin "1") (pinfunction "1_1") (pintype "passive"))
      (node (ref "EPD_C10") (pin "1") (pinfunction "1_1") (pintype "passive"))
      (node (ref "EPD_C11") (pin "1") (pinfunction "1_1") (pintype "passive"))
      (node (ref "EPD_C12") (pin "1") (pinfunction "1_1") (pintype "passive"))
      (node (ref "EPD_C2") (pin "2") (pinfunction "2_2") (pintype "passive"))
      (node (ref "EPD_C5") (pin "1") (pinfunction "1_1") (pintype "passive"))
      (node (ref "EPD_C6") (pin "1") (pinfunction "1_1") (pintype "passive"))
      (node (ref "EPD_C7") (pin "1") (pinfunction "1_1") (pintype "passive"))
      (node (ref "EPD_C8") (pin "1") (pinfunction "1_1") (pintype "passive"))
      (node (ref "EPD_C9") (pin "1") (pinfunction "1_1") (pintype "passive"))
      (node (ref "IC1") (pin "D2") (pinfunction "GND_D2") (pintype "bidirectional"))
      (node (ref "IC2") (pin "B1") (pinfunction "IN/TRIG_B1") (pintype "bidirectional"))
      (node (ref "IC2") (pin "B3") (pinfunction "GND_B3") (pintype "bidirectional"))
      (node (ref "IC3") (pin "8") (pinfunction "GNDIO_8") (pintype "bidirectional"))
      (node (ref "IC3") (pin "9") (pinfunction "GND_9") (pintype "bidirectional"))
      (node (ref "IC9") (pin "A1") (pinfunction "EN_A1") (pintype "bidirectional"))
      (node (ref "IC9") (pin "A2") (pinfunction "VIN_1_A2") (pintype "bidirectional"))
      (node (ref "IC9") (pin "A3") (pinfunction "VIN_2_A3") (pintype "bidirectional"))
      (node (ref "IC9") (pin "B1") (pinfunction "VSEL_B1") (pintype "bidirectional"))
      (node (ref "IC9") (pin "C1") (pinfunction "AGND_C1") (pintype "bidirectional"))
      (node (ref "IC9") (pin "C2") (pinfunction "PGND_1_C2") (pintype "bidirectional"))
      (node (ref "IC9") (pin "C3") (pinfunction "PGND_2_C3") (pintype "bidirectional"))
      (node (ref "J1") (pin "17") (pinfunction "17_17") (pintype "bidirectional"))
      (node (ref "J1") (pin "8") (pinfunction "8_8") (pintype "bidirectional"))
      (node (ref "J1") (pin "MP1") (pinfunction "MP1_MP1") (pintype "bidirectional"))
      (node (ref "J1") (pin "MP2") (pinfunction "MP2_MP2") (pintype "bidirectional"))
      (node (ref "J2") (pin "3") (pinfunction "3_3") (pintype "bidirectional"))
      (node (ref "J2") (pin "5") (pinfunction "5_5") (pintype "bidirectional"))
      (node (ref "J4") (pin "A12_B1") (pinfunction "GND_A12_B1") (pintype "power_in"))
      (node (ref "J4") (pin "A1_B12") (pinfunction "GND_A1_B12") (pintype "power_in"))
      (node (ref "J4") (pin "SH1") (pinfunction "SHIELD_SH1") (pintype "passive"))
      (node (ref "J4") (pin "SH2") (pinfunction "SHIELD_SH2") (pintype "passive"))
      (node (ref "J4") (pin "SH3") (pinfunction "SHIELD_SH3") (pintype "passive"))
      (node (ref "J4") (pin "SH4") (pinfunction "SHIELD_SH4") (pintype "passive"))
      (node (ref "R1_USB") (pin "1") (pinfunction "1_1") (pintype "bidirectional"))
      (node (ref "R1_USB1") (pin "2") (pinfunction "2_2") (pintype "bidirectional"))
      (node (ref "R2_EP_DR") (pin "1") (pinfunction "1_1") (pintype "bidirectional"))
      (node (ref "R3") (pin "1") (pinfunction "1_1") (pintype "bidirectional"))
      (node (ref "R9") (pin "1") (pinfunction "1_1") (pintype "bidirectional"))
      (node (ref "R_TYPE_SEL") (pin "1") (pinfunction "1_1") (pintype "bidirectional"))
      (node (ref "SJ1") (pin "1") (pinfunction "1_1") (pintype "passive"))
      (node (ref "SW_DN") (pin "1") (pinfunction "1_1") (pintype "passive"))
      (node (ref "SW_ENT") (pin "1") (pinfunction "1_1") (pintype "passive"))
      (node (ref "SW_UP") (pin "1") (pinfunction "1_1") (pintype "passive"))
      (node (ref "U$1") (pin "P$74") (pinfunction "VSS_PAD_P$74") (pintype "bidirectional"))
      (node (ref "U$1") (pin "P$75") (pinfunction "VSS_PAD_P$75") (pintype "bidirectional"))
      (node (ref "U$1") (pin "P$76") (pinfunction "VSS_PAD_P$76") (pintype "bidirectional"))
      (node (ref "U$1") (pin "P$77") (pinfunction "VSS_PAD_P$77") (pintype "bidirectional"))
      (node (ref "U$1") (pin "P$78") (pinfunction "VSS_PAD_P$78") (pintype "bidirectional"))
      (node (ref "U$1") (pin "P$79") (pinfunction "VSS_PAD_P$79") (pintype "bidirectional"))
      (node (ref "U$1") (pin "P$80") (pinfunction "VSS_PAD_P$80") (pintype "bidirectional"))
      (node (ref "U$1") (pin "P$81") (pinfunction "VSS_PAD_P$81") (pintype "bidirectional"))
      (node (ref "U$1") (pin "P$82") (pinfunction "VSS_PAD_P$82") (pintype "bidirectional"))
      (node (ref "U$1") (pin "P$83") (pinfunction "VSS_PAD_P$83") (pintype "bidirectional"))
      (node (ref "U$1") (pin "P$84") (pinfunction "VSS_PAD_P$84") (pintype "bidirectional"))
      (node (ref "U$1") (pin "P$85") (pinfunction "VSS_PAD_P$85") (pintype "bidirectional"))
      (node (ref "U$1") (pin "P$86") (pinfunction "VSS_PAD_P$86") (pintype "bidirectional"))
      (node (ref "U$1") (pin "P$87") (pinfunction "VSS_PAD_P$87") (pintype "bidirectional"))
      (node (ref "U$1") (pin "P$88") (pinfunction "VSS_PAD_P$88") (pintype "bidirectional"))
      (node (ref "U$1") (pin "P$89") (pinfunction "VSS_PAD_P$89") (pintype "bidirectional"))
      (node (ref "U$1") (pin "P$90") (pinfunction "VSS_PAD_P$90") (pintype "bidirectional"))
      (node (ref "U$1") (pin "P$B7") (pinfunction "VSS_P$B7") (pintype "power_in"))
      (node (ref "U$1") (pin "P$F23") (pinfunction "VSS_PA_P$F23") (pintype "bidirectional"))
      (node (ref "U3") (pin "1") (pinfunction "CTG_1") (pintype "power_in"))
      (node (ref "U3") (pin "4") (pinfunction "GND_4") (pintype "power_in"))
      (node (ref "U3") (pin "6") (pinfunction "QSTRT_6") (pintype "input"))
      (node (ref "U3") (pin "9") (pinfunction "EP_9") (pintype "power_in"))
      (node (ref "X1") (pin "2") (pinfunction "2_2") (pintype "passive"))
      (node (ref "X1") (pin "4") (pinfunction "4_4") (pintype "passive"))
    )
    (net (code "22") (name "HAPTIC_EN{slash}1.4C") (class "Default")
      (node (ref "IC2") (pin "A1") (pinfunction "EN_A1") (pintype "bidirectional"))
    )
    (net (code "23") (name "HAPTIC_EN{slash}2.6A") (class "Default")
      (node (ref "U$1") (pin "P$U1") (pinfunction "P0.12_P$U1") (pintype "bidirectional"))
    )
    (net (code "24") (name "IMU_INT1") (class "Default")
      (node (ref "IC3") (pin "5") (pinfunction "INT1_5") (pintype "bidirectional"))
      (node (ref "U$1") (pin "P$N1") (pinfunction "P0.08_P$N1") (pintype "bidirectional"))
    )
    (net (code "25") (name "IMU_INT2") (class "Default")
      (node (ref "IC3") (pin "6") (pinfunction "INT2_6") (pintype "bidirectional"))
      (node (ref "U$1") (pin "P$P2") (pinfunction "P1.08_P$P2") (pintype "bidirectional"))
    )
    (net (code "26") (name "LX1") (class "Default")
      (node (ref "IC9") (pin "B2") (pinfunction "SW1_1_B2") (pintype "bidirectional"))
      (node (ref "IC9") (pin "B3") (pinfunction "SW1_2_B3") (pintype "bidirectional"))
      (node (ref "L7") (pin "1") (pinfunction "1_1") (pintype "bidirectional"))
    )
    (net (code "27") (name "LX2") (class "Default")
      (node (ref "IC9") (pin "D2") (pinfunction "SW2_1_D2") (pintype "bidirectional"))
      (node (ref "IC9") (pin "D3") (pinfunction "SW2_2_D3") (pintype "bidirectional"))
      (node (ref "L7") (pin "2") (pinfunction "2_2") (pintype "bidirectional"))
    )
    (net (code "28") (name "MOSI{slash}1.5B") (class "Default")
      (node (ref "J1") (pin "14") (pinfunction "14_14") (pintype "bidirectional"))
    )
    (net (code "29") (name "MOSI{slash}2.2D") (class "Default")
      (node (ref "U$1") (pin "P$B13") (pinfunction "P0.03/AIN1_P$B13") (pintype "bidirectional"))
    )
    (net (code "30") (name "Net-(ANT1-FEED)") (class "Default")
      (node (ref "ANT1") (pin "1") (pinfunction "FEED_1") (pintype "input"))
      (node (ref "C22") (pin "1") (pinfunction "1_1") (pintype "passive"))
      (node (ref "C4") (pin "1") (pinfunction "1_1") (pintype "passive"))
      (node (ref "L1") (pin "2") (pinfunction "2_2") (pintype "bidirectional"))
    )
    (net (code "31") (name "Net-(D2-K)") (class "Default")
      (node (ref "C2_EP_DR") (pin "2") (pinfunction "2_2") (pintype "passive"))
      (node (ref "D2") (pin "1") (pinfunction "K_1") (pintype "bidirectional"))
      (node (ref "D4") (pin "2") (pinfunction "A_2") (pintype "bidirectional"))
    )
    (net (code "32") (name "Net-(D5-A)") (class "Default")
      (node (ref "C2_EP_DR") (pin "1") (pinfunction "1_1") (pintype "passive"))
      (node (ref "D5") (pin "2") (pinfunction "A_2") (pintype "bidirectional"))
      (node (ref "L5") (pin "2") (pinfunction "2_2") (pintype "passive"))
      (node (ref "Q3") (pin "3") (pinfunction "D_3") (pintype "bidirectional"))
    )
    (net (code "33") (name "Net-(EPD_C1-Pad2)") (class "Default")
      (node (ref "EPD_C1") (pin "2") (pinfunction "2_2") (pintype "passive"))
      (node (ref "J1") (pin "5") (pinfunction "5_5") (pintype "bidirectional"))
    )
    (net (code "34") (name "Net-(EPD_C2-Pad1)") (class "Default")
      (node (ref "EPD_C2") (pin "1") (pinfunction "1_1") (pintype "passive"))
      (node (ref "J1") (pin "4") (pinfunction "4_4") (pintype "bidirectional"))
    )
    (net (code "35") (name "Net-(EPD_C6-Pad2)") (class "Default")
      (node (ref "EPD_C6") (pin "2") (pinfunction "2_2") (pintype "passive"))
      (node (ref "J1") (pin "18") (pinfunction "18_18") (pintype "bidirectional"))
    )
    (net (code "36") (name "Net-(EPD_C7-Pad2)") (class "Default")
      (node (ref "EPD_C7") (pin "2") (pinfunction "2_2") (pintype "passive"))
      (node (ref "J1") (pin "19") (pinfunction "19_19") (pintype "bidirectional"))
    )
    (net (code "37") (name "Net-(EPD_C8-Pad2)") (class "Default")
      (node (ref "EPD_C8") (pin "2") (pinfunction "2_2") (pintype "passive"))
      (node (ref "J1") (pin "20") (pinfunction "20_20") (pintype "bidirectional"))
    )
    (net (code "38") (name "Net-(EPD_C10-Pad2)") (class "Default")
      (node (ref "EPD_C10") (pin "2") (pinfunction "2_2") (pintype "passive"))
      (node (ref "J1") (pin "22") (pinfunction "22_22") (pintype "bidirectional"))
    )
    (net (code "39") (name "Net-(EPD_C12-Pad2)") (class "Default")
      (node (ref "EPD_C12") (pin "2") (pinfunction "2_2") (pintype "passive"))
      (node (ref "J1") (pin "24") (pinfunction "24_24") (pintype "bidirectional"))
    )
    (net (code "40") (name "Net-(IC1-TS{slash}MR)") (class "Default")
      (node (ref "IC1") (pin "D1") (pinfunction "TS/MR_D1") (pintype "bidirectional"))
      (node (ref "R9") (pin "2") (pinfunction "2_2") (pintype "bidirectional"))
    )
    (net (code "41") (name "Net-(IC2-REG)") (class "Default")
      (node (ref "C32") (pin "2") (pinfunction "2_2") (pintype "passive"))
      (node (ref "IC2") (pin "A2") (pinfunction "REG_A2") (pintype "bidirectional"))
    )
    (net (code "42") (name "Net-(IC3-SDO)") (class "Default")
      (node (ref "IC3") (pin "1") (pinfunction "SDO_1") (pintype "bidirectional"))
      (node (ref "R3") (pin "2") (pinfunction "2_2") (pintype "bidirectional"))
    )
    (net (code "43") (name "Net-(IC9-SCL)") (class "Default")
      (node (ref "IC9") (pin "D1") (pinfunction "SCL_D1") (pintype "bidirectional"))
      (node (ref "R4") (pin "2") (pinfunction "2_2") (pintype "bidirectional"))
    )
    (net (code "44") (name "Net-(IC9-SDA)") (class "Default")
      (node (ref "IC9") (pin "E1") (pinfunction "SDA_E1") (pintype "bidirectional"))
      (node (ref "R2") (pin "2") (pinfunction "2_2") (pintype "bidirectional"))
    )
    (net (code "45") (name "Net-(J4-CC1)") (class "Default")
      (node (ref "J4") (pin "A5") (pinfunction "CC1_A5") (pintype "bidirectional"))
      (node (ref "R1_USB") (pin "2") (pinfunction "2_2") (pintype "bidirectional"))
    )
    (net (code "46") (name "Net-(J4-CC2)") (class "Default")
      (node (ref "J4") (pin "B5") (pinfunction "CC2_B5") (pintype "bidirectional"))
      (node (ref "R1_USB1") (pin "1") (pinfunction "1_1") (pintype "bidirectional"))
    )
    (net (code "47") (name "Net-(L2-Pad2)") (class "Default")
      (node (ref "L2") (pin "2") (pinfunction "2_2") (pintype "bidirectional"))
      (node (ref "L3") (pin "1") (pinfunction "1_1") (pintype "bidirectional"))
    )
    (net (code "48") (name "Net-(R1_EP_DR-Pad1)") (class "Default")
      (node (ref "R1_EP_DR") (pin "1") (pinfunction "1_1") (pintype "bidirectional"))
      (node (ref "R_TYPE_SEL") (pin "2") (pinfunction "2_2") (pintype "bidirectional"))
      (node (ref "SJ1") (pin "2") (pinfunction "2_2") (pintype "passive"))
    )
    (net (code "49") (name "Net-(U$1-ANT)") (class "Default")
      (node (ref "C3") (pin "1") (pinfunction "1_1") (pintype "passive"))
      (node (ref "L1") (pin "1") (pinfunction "1_1") (pintype "bidirectional"))
      (node (ref "U$1") (pin "P$H23") (pinfunction "ANT_P$H23") (pintype "bidirectional"))
    )
    (net (code "50") (name "Net-(U$1-DCC)") (class "Default")
      (node (ref "L2") (pin "1") (pinfunction "1_1") (pintype "bidirectional"))
      (node (ref "U$1") (pin "P$B3") (pinfunction "DCC_P$B3") (pintype "output"))
    )
    (net (code "51") (name "Net-(U$1-DEC1)") (class "Default")
      (node (ref "C5") (pin "1") (pinfunction "1_1") (pintype "passive"))
      (node (ref "U$1") (pin "P$C1") (pinfunction "DEC1_P$C1") (pintype "power_in"))
    )
    (net (code "52") (name "Net-(U$1-DEC2)") (class "Default")
      (node (ref "C13") (pin "1") (pinfunction "1_1") (pintype "passive"))
      (node (ref "U$1") (pin "P$A18") (pinfunction "DEC2_P$A18") (pintype "bidirectional"))
    )
    (net (code "53") (name "Net-(U$1-DEC3)") (class "Default")
      (node (ref "C11") (pin "1") (pinfunction "1_1") (pintype "passive"))
      (node (ref "U$1") (pin "P$D23") (pinfunction "DEC3_P$D23") (pintype "bidirectional"))
    )
    (net (code "54") (name "Net-(U$1-DEC3V3)") (class "Default")
      (node (ref "C20") (pin "1") (pinfunction "1_1") (pintype "passive"))
      (node (ref "U$1") (pin "P$AC5") (pinfunction "DEC3V3_P$AC5") (pintype "bidirectional"))
    )
    (net (code "55") (name "Net-(U$1-DEC4)") (class "Default")
      (node (ref "C10") (pin "1") (pinfunction "1_1") (pintype "passive"))
      (node (ref "C15") (pin "1") (pinfunction "1_1") (pintype "passive"))
      (node (ref "C16") (pin "1") (pinfunction "1_1") (pintype "passive"))
      (node (ref "L3") (pin "2") (pinfunction "2_2") (pintype "bidirectional"))
      (node (ref "U$1") (pin "P$B5") (pinfunction "DEC4_P$B5") (pintype "power_in"))
      (node (ref "U$1") (pin "P$E24") (pinfunction "DEC6_P$E24") (pintype "bidirectional"))
    )
    (net (code "56") (name "Net-(U$1-DEC5)") (class "Default")
      (node (ref "C9") (pin "1") (pinfunction "1_1") (pintype "passive"))
      (node (ref "U$1") (pin "P$N24") (pinfunction "DEC5_P$N24") (pintype "bidirectional"))
    )
    (net (code "57") (name "Net-(U$1-P0.00{slash}XL1)") (class "Default")
      (node (ref "C17") (pin "2") (pinfunction "2_2") (pintype "passive"))
      (node (ref "U$1") (pin "P$D2") (pinfunction "P0.00/XL1_P$D2") (pintype "bidirectional"))
      (node (ref "X2") (pin "1") (pinfunction "1_1") (pintype "passive"))
    )
    (net (code "58") (name "Net-(U$1-P0.01{slash}XL2)") (class "Default")
      (node (ref "C18") (pin "2") (pinfunction "2_2") (pintype "passive"))
      (node (ref "U$1") (pin "P$F2") (pinfunction "P0.01/XL2_P$F2") (pintype "bidirectional"))
      (node (ref "X2") (pin "2") (pinfunction "2_2") (pintype "passive"))
    )
    (net (code "59") (name "Net-(U$1-XC1)") (class "Default")
      (node (ref "C1") (pin "1") (pinfunction "1_1") (pintype "passive"))
      (node (ref "U$1") (pin "P$B24") (pinfunction "XC1_P$B24") (pintype "input"))
      (node (ref "X1") (pin "1") (pinfunction "1_1") (pintype "passive"))
    )
    (net (code "60") (name "Net-(U$1-XC2)") (class "Default")
      (node (ref "C2") (pin "1") (pinfunction "1_1") (pintype "passive"))
      (node (ref "U$1") (pin "P$A23") (pinfunction "XC2_P$A23") (pintype "output"))
      (node (ref "X1") (pin "3") (pinfunction "3_3") (pintype "passive"))
    )
    (net (code "61") (name "OUT+") (class "Default")
      (node (ref "IC2") (pin "A3") (pinfunction "OUT+_A3") (pintype "bidirectional"))
    )
    (net (code "62") (name "OUT-") (class "Default")
      (node (ref "IC2") (pin "C3") (pinfunction "OUT-_C3") (pintype "bidirectional"))
    )
    (net (code "63") (name "P.014{slash}2.7C") (class "Default")
      (node (ref "U$1") (pin "P$AC9") (pinfunction "P0.14_P$AC9") (pintype "bidirectional"))
    )
    (net (code "64") (name "P0.04") (class "Default")
      (node (ref "U$1") (pin "P$J1") (pinfunction "P0.04/AIN2_P$J1") (pintype "bidirectional"))
    )
    (net (code "65") (name "P0.09") (class "Default")
      (node (ref "U$1") (pin "P$L24") (pinfunction "P0.09/NFC1_P$L24") (pintype "bidirectional"))
    )
    (net (code "66") (name "P0.13{slash}1.5D") (class "Default")
      (node (ref "C30") (pin "2") (pinfunction "2_2") (pintype "passive"))
      (node (ref "R5") (pin "1") (pinfunction "1_1") (pintype "bidirectional"))
      (node (ref "SW_UP") (pin "2") (pinfunction "2_2") (pintype "passive"))
    )
    (net (code "67") (name "P0.13{slash}2.6C") (class "Default")
      (node (ref "U$1") (pin "P$AD8") (pinfunction "P0.13_P$AD8") (pintype "bidirectional"))
    )
    (net (code "68") (name "P0.14{slash}1.5D") (class "Default")
      (node (ref "C31") (pin "2") (pinfunction "2_2") (pintype "passive"))
      (node (ref "R8") (pin "1") (pinfunction "1_1") (pintype "bidirectional"))
      (node (ref "SW_ENT") (pin "2") (pinfunction "2_2") (pintype "passive"))
    )
    (net (code "69") (name "P0.19") (class "Default")
      (node (ref "U$1") (pin "P$AC15") (pinfunction "P0.19_P$AC15") (pintype "bidirectional"))
    )
    (net (code "70") (name "P0.20") (class "Default")
      (node (ref "U$1") (pin "P$AD16") (pinfunction "P0.20_P$AD16") (pintype "bidirectional"))
    )
    (net (code "71") (name "P0.21") (class "Default")
      (node (ref "U$1") (pin "P$AC17") (pinfunction "P0.21_P$AC17") (pintype "bidirectional"))
    )
    (net (code "72") (name "P0.22") (class "Default")
      (node (ref "U$1") (pin "P$AD18") (pinfunction "P0.22_P$AD18") (pintype "bidirectional"))
    )
    (net (code "73") (name "P0.23") (class "Default")
      (node (ref "U$1") (pin "P$AC19") (pinfunction "P0.23_P$AC19") (pintype "bidirectional"))
    )
    (net (code "74") (name "P0.24") (class "Default")
      (node (ref "U$1") (pin "P$AD20") (pinfunction "P0.24_P$AD20") (pintype "bidirectional"))
    )
    (net (code "75") (name "P0.25") (class "Default")
      (node (ref "U$1") (pin "P$AC21") (pinfunction "P0.25_P$AC21") (pintype "bidirectional"))
    )
    (net (code "76") (name "P0.26") (class "Default")
      (node (ref "U$1") (pin "P$G1") (pinfunction "P0.26_P$G1") (pintype "bidirectional"))
    )
    (net (code "77") (name "P0.27") (class "Default")
      (node (ref "U$1") (pin "P$H2") (pinfunction "P0.27_P$H2") (pintype "bidirectional"))
    )
    (net (code "78") (name "P0.28") (class "Default")
      (node (ref "U$1") (pin "P$B11") (pinfunction "P0.28/AIN4_P$B11") (pintype "bidirectional"))
    )
    (net (code "79") (name "P0.29") (class "Default")
      (node (ref "U$1") (pin "P$A10") (pinfunction "P0.29/AIN5_P$A10") (pintype "bidirectional"))
    )
    (net (code "80") (name "P0.30") (class "Default")
      (node (ref "U$1") (pin "P$B9") (pinfunction "P0.30/AIN6_P$B9") (pintype "bidirectional"))
    )
    (net (code "81") (name "P0.31") (class "Default")
      (node (ref "U$1") (pin "P$A8") (pinfunction "P0.31/AIN7_P$A8") (pintype "bidirectional"))
    )
    (net (code "82") (name "P1.01{slash}1.6C") (class "Default")
      (node (ref "Q1") (pin "1") (pinfunction "G_1") (pintype "bidirectional"))
      (node (ref "R_PWR_EPD") (pin "1") (pinfunction "1_1") (pintype "bidirectional"))
    )
    (net (code "83") (name "P1.01{slash}2.4B") (class "Default")
      (node (ref "U$1") (pin "P$Y23") (pinfunction "P1.01_P$Y23") (pintype "bidirectional"))
    )
    (net (code "84") (name "P1.02{slash}1.6C") (class "Default")
      (node (ref "C29") (pin "2") (pinfunction "2_2") (pintype "passive"))
      (node (ref "R7") (pin "1") (pinfunction "1_1") (pintype "bidirectional"))
      (node (ref "SW_DN") (pin "2") (pinfunction "2_2") (pintype "passive"))
    )
    (net (code "85") (name "P1.02{slash}2.8C") (class "Default")
      (node (ref "U$1") (pin "P$W24") (pinfunction "P1.02_P$W24") (pintype "bidirectional"))
    )
    (net (code "86") (name "P1.03") (class "Default")
      (node (ref "U$1") (pin "P$V23") (pinfunction "P1.03_P$V23") (pintype "bidirectional"))
    )
    (net (code "87") (name "P1.04") (class "Default")
      (node (ref "U$1") (pin "P$U24") (pinfunction "P1.04_P$U24") (pintype "bidirectional"))
    )
    (net (code "88") (name "P1.05") (class "Default")
      (node (ref "U$1") (pin "P$T23") (pinfunction "P1.05_P$T23") (pintype "bidirectional"))
    )
    (net (code "89") (name "P1.06") (class "Default")
      (node (ref "U$1") (pin "P$R24") (pinfunction "P1.06_P$R24") (pintype "bidirectional"))
    )
    (net (code "90") (name "P1.07") (class "Default")
      (node (ref "U$1") (pin "P$P23") (pinfunction "P1.07_P$P23") (pintype "bidirectional"))
    )
    (net (code "91") (name "P1.09") (class "Default")
      (node (ref "U$1") (pin "P$R1") (pinfunction "P1.09_P$R1") (pintype "bidirectional"))
    )
    (net (code "92") (name "P1.10") (class "Default")
      (node (ref "U$1") (pin "P$A20") (pinfunction "P1.10_P$A20") (pintype "bidirectional"))
    )
    (net (code "93") (name "P1.11") (class "Default")
      (node (ref "U$1") (pin "P$B19") (pinfunction "P1.11_P$B19") (pintype "bidirectional"))
    )
    (net (code "94") (name "P1.12") (class "Default")
      (node (ref "U$1") (pin "P$B17") (pinfunction "P1.12_P$B17") (pintype "bidirectional"))
    )
    (net (code "95") (name "P1.13") (class "Default")
      (node (ref "U$1") (pin "P$A16") (pinfunction "P1.13_P$A16") (pintype "bidirectional"))
    )
    (net (code "96") (name "P1.14") (class "Default")
      (node (ref "U$1") (pin "P$B15") (pinfunction "P1.14_P$B15") (pintype "bidirectional"))
    )
    (net (code "97") (name "P1.15") (class "Default")
      (node (ref "U$1") (pin "P$A14") (pinfunction "P1.15_P$A14") (pintype "bidirectional"))
    )
    (net (code "98") (name "PMIC_INT") (class "Default")
      (node (ref "IC1") (pin "A1") (pinfunction "~{INT}_A1") (pintype "bidirectional"))
      (node (ref "U$1") (pin "P$T2") (pinfunction "P0.11_P$T2") (pintype "bidirectional"))
    )
    (net (code "99") (name "PREVGH") (class "Default")
      (node (ref "D5") (pin "1") (pinfunction "K_1") (pintype "bidirectional"))
      (node (ref "EPD_C9") (pin "2") (pinfunction "2_2") (pintype "passive"))
      (node (ref "J1") (pin "21") (pinfunction "21_21") (pintype "bidirectional"))
    )
    (net (code "100") (name "PREVGL") (class "Default")
      (node (ref "D2") (pin "2") (pinfunction "A_2") (pintype "bidirectional"))
      (node (ref "EPD_C11") (pin "2") (pinfunction "2_2") (pintype "passive"))
      (node (ref "J1") (pin "23") (pinfunction "23_23") (pintype "bidirectional"))
    )
    (net (code "101") (name "RESET") (class "Default")
      (node (ref "J1") (pin "3") (pinfunction "3_3") (pintype "bidirectional"))
      (node (ref "J2") (pin "6") (pinfunction "6_6") (pintype "bidirectional"))
      (node (ref "Q3") (pin "2") (pinfunction "S_2") (pintype "bidirectional"))
      (node (ref "R1_EP_DR") (pin "2") (pinfunction "2_2") (pintype "bidirectional"))
      (node (ref "U$1") (pin "P$AC13") (pinfunction "P0.18/RESET_P$AC13") (pintype "bidirectional"))
    )
    (net (code "102") (name "SCK{slash}1.5B") (class "Default")
      (node (ref "J1") (pin "13") (pinfunction "13_13") (pintype "bidirectional"))
    )
    (net (code "103") (name "SCK{slash}2.2D") (class "Default")
      (node (ref "U$1") (pin "P$A12") (pinfunction "P0.02/AIN0_P$A12") (pintype "bidirectional"))
    )
    (net (code "104") (name "SCL{slash}1.4C") (class "Default")
      (node (ref "IC2") (pin "C1") (pinfunction "SCL_C1") (pintype "bidirectional"))
      (node (ref "U3") (pin "7") (pinfunction "SCL_7") (pintype "input"))
    )
    (net (code "105") (name "SCL{slash}2.4C") (class "Default")
      (node (ref "IC1") (pin "B1") (pinfunction "SCL_B1") (pintype "bidirectional"))
      (node (ref "IC3") (pin "12") (pinfunction "SCX_12") (pintype "bidirectional"))
      (node (ref "R17") (pin "2") (pinfunction "2_2") (pintype "bidirectional"))
      (node (ref "R4") (pin "1") (pinfunction "1_1") (pintype "bidirectional"))
      (node (ref "U$1") (pin "P$M2") (pinfunction "P0.07_P$M2") (pintype "bidirectional"))
    )
    (net (code "106") (name "SDA{slash}1.4C") (class "Default")
      (node (ref "IC2") (pin "B2") (pinfunction "SDA_B2") (pintype "bidirectional"))
      (node (ref "U3") (pin "8") (pinfunction "SDA_8") (pintype "bidirectional"))
    )
    (net (code "107") (name "SDA{slash}2.4C") (class "Default")
      (node (ref "IC1") (pin "C1") (pinfunction "SDA_C1") (pintype "bidirectional"))
      (node (ref "IC3") (pin "2") (pinfunction "SDX_2") (pintype "bidirectional"))
      (node (ref "R18") (pin "2") (pinfunction "2_2") (pintype "bidirectional"))
      (node (ref "R2") (pin "1") (pinfunction "1_1") (pintype "bidirectional"))
      (node (ref "U$1") (pin "P$L1") (pinfunction "P0.06_P$L1") (pintype "bidirectional"))
    )
    (net (code "108") (name "SWDCLK") (class "Default")
      (node (ref "J2") (pin "4") (pinfunction "4_4") (pintype "bidirectional"))
      (node (ref "U$1") (pin "P$AA24") (pinfunction "SWDCLK_P$AA24") (pintype "input"))
    )
    (net (code "109") (name "SWDIO") (class "Default")
      (node (ref "J2") (pin "2") (pinfunction "2_2") (pintype "bidirectional"))
      (node (ref "U$1") (pin "P$AC24") (pinfunction "SWDIO_P$AC24") (pintype "bidirectional"))
    )
    (net (code "110") (name "SWO") (class "Default")
      (node (ref "U$1") (pin "P$AD22") (pinfunction "P1.00_P$AD22") (pintype "bidirectional"))
    )
    (net (code "111") (name "VBAT{slash}1.2A") (class "Default")
      (node (ref "C27") (pin "2") (pinfunction "2_2") (pintype "passive"))
      (node (ref "U3") (pin "2") (pinfunction "CELL_2") (pintype "power_in"))
      (node (ref "U3") (pin "3") (pinfunction "VDD_3") (pintype "power_in"))
    )
    (net (code "112") (name "VBAT{slash}2.5C") (class "Default")
      (node (ref "C37") (pin "2") (pinfunction "2_2") (pintype "passive"))
      (node (ref "IC1") (pin "C2") (pinfunction "BAT_C2") (pintype "bidirectional"))
    )
    (net (code "113") (name "VBUS{slash}1.5D") (class "Default")
      (node (ref "C42") (pin "2") (pinfunction "2_2") (pintype "passive"))
      (node (ref "C43") (pin "1") (pinfunction "1_1") (pintype "passive"))
      (node (ref "D3") (pin "5") (pinfunction "VBUS_5") (pintype "bidirectional"))
      (node (ref "J4") (pin "A4_B9") (pinfunction "VBUS_A4_B9") (pintype "power_in"))
      (node (ref "J4") (pin "A9_B4") (pinfunction "VBUS_A9_B4") (pintype "power_in"))
    )
    (net (code "114") (name "VBUS{slash}2.6D") (class "Default")
      (node (ref "C21") (pin "1") (pinfunction "1_1") (pintype "passive"))
      (node (ref "C38") (pin "2") (pinfunction "2_2") (pintype "passive"))
      (node (ref "IC1") (pin "A2") (pinfunction "IN_A2") (pintype "bidirectional"))
      (node (ref "U$1") (pin "P$AD2") (pinfunction "VBUS_P$AD2") (pintype "power_in"))
    )
    (net (code "115") (name "VREG") (class "Default")
      (node (ref "C39") (pin "2") (pinfunction "2_2") (pintype "passive"))
      (node (ref "IC1") (pin "B2") (pinfunction "SYS_B2") (pintype "bidirectional"))
    )
    (net (code "116") (name "unconnected-(ANT1-NC-Pad2)") (class "Default")
      (node (ref "ANT1") (pin "2") (pinfunction "NC_2") (pintype "no_connect"))
    )
    (net (code "117") (name "unconnected-(IC3-ASCL-Pad11)") (class "Default")
      (node (ref "IC3") (pin "11") (pinfunction "ASCL_11") (pintype "bidirectional"))
    )
    (net (code "118") (name "unconnected-(IC3-ASDA-Pad4)") (class "Default")
      (node (ref "IC3") (pin "4") (pinfunction "ASDA_4") (pintype "bidirectional"))
    )
    (net (code "119") (name "unconnected-(J1-Pad1)") (class "Default")
      (node (ref "J1") (pin "1") (pinfunction "1_1") (pintype "bidirectional"))
    )
    (net (code "120") (name "unconnected-(J1-Pad6)") (class "Default")
      (node (ref "J1") (pin "6") (pinfunction "6_6") (pintype "bidirectional"))
    )
    (net (code "121") (name "unconnected-(J1-Pad7)") (class "Default")
      (node (ref "J1") (pin "7") (pinfunction "7_7") (pintype "bidirectional"))
    )
    (net (code "122") (name "unconnected-(J4-SBU1-PadA8)") (class "Default")
      (node (ref "J4") (pin "A8") (pinfunction "SBU1_A8") (pintype "bidirectional"))
    )
    (net (code "123") (name "unconnected-(J4-SBU2-PadB8)") (class "Default")
      (node (ref "J4") (pin "B8") (pinfunction "SBU2_B8") (pintype "bidirectional"))
    )
    (net (code "124") (name "unconnected-(U$1-DCCH-PadP$AB2)") (class "Default")
      (node (ref "U$1") (pin "P$AB2") (pinfunction "DCCH_P$AB2") (pintype "bidirectional"))
    )
  )
)
